# ram.net
KiCad netlist of a schematic drawn in EAGLE
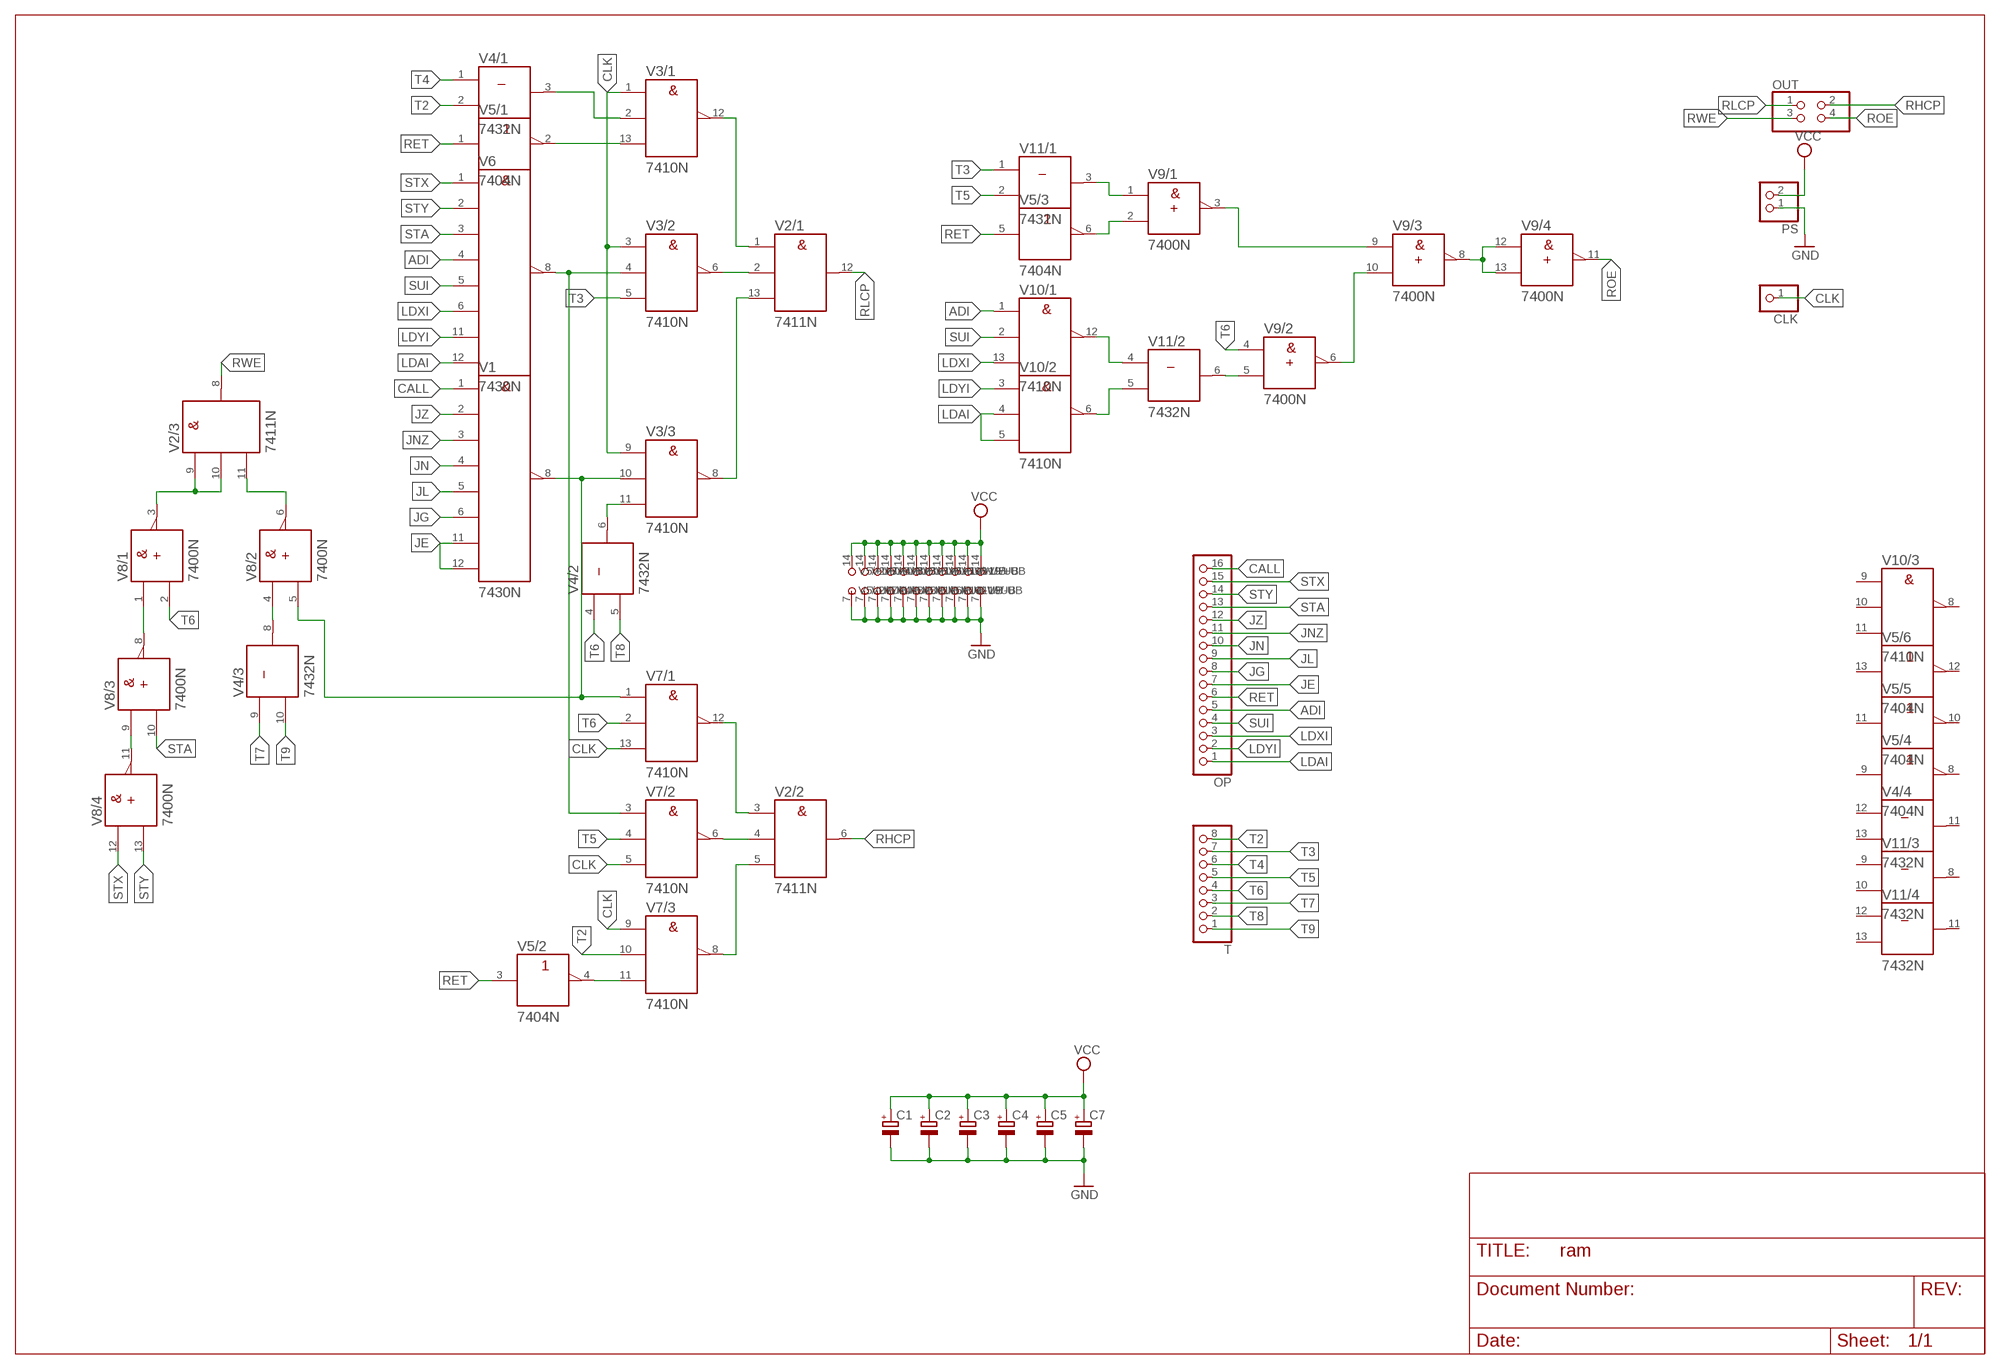
[diagram p0: schematic, sheet 1]

(export (version "E")
  (design (tool "Eeschema 10.0.6"))
  (components
    (comp (ref "C1")
      (value "CPOL-EUE2.5-6")
      (footprint "eagle-import:E2,5-6")
      (libsource (lib "eagle-import") (part "CPOL-EUE2.5-6"))
    )
    (comp (ref "C2")
      (value "CPOL-EUE2.5-6")
      (footprint "eagle-import:E2,5-6")
      (libsource (lib "eagle-import") (part "CPOL-EUE2.5-6"))
    )
    (comp (ref "C3")
      (value "CPOL-EUE2.5-6")
      (footprint "eagle-import:E2,5-6")
      (libsource (lib "eagle-import") (part "CPOL-EUE2.5-6"))
    )
    (comp (ref "C4")
      (value "CPOL-EUE2.5-6")
      (footprint "eagle-import:E2,5-6")
      (libsource (lib "eagle-import") (part "CPOL-EUE2.5-6"))
    )
    (comp (ref "C5")
      (value "CPOL-EUE2.5-6")
      (footprint "eagle-import:E2,5-6")
      (libsource (lib "eagle-import") (part "CPOL-EUE2.5-6"))
    )
    (comp (ref "C7")
      (value "CPOL-EUE2.5-6")
      (footprint "eagle-import:E2,5-6")
      (libsource (lib "eagle-import") (part "CPOL-EUE2.5-6"))
    )
    (comp (ref "CLK")
      (value "PINHD-1X1")
      (footprint "eagle-import:1X01")
      (libsource (lib "eagle-import") (part "PINHD-1X1"))
    )
    (comp (ref "OP")
      (value "PINHD-1X16")
      (footprint "eagle-import:1X16")
      (libsource (lib "eagle-import") (part "PINHD-1X16"))
    )
    (comp (ref "OUT")
      (value "PINHD-2X2")
      (footprint "eagle-import:2X02")
      (libsource (lib "eagle-import") (part "PINHD-2X2"))
    )
    (comp (ref "PS")
      (value "PINHD-1X2")
      (footprint "eagle-import:1X02")
      (libsource (lib "eagle-import") (part "PINHD-1X2"))
    )
    (comp (ref "T")
      (value "PINHD-1X8")
      (footprint "eagle-import:1X08")
      (libsource (lib "eagle-import") (part "PINHD-1X8"))
    )
    (comp (ref "V1")
      (value "7430N")
      (footprint "eagle-import:DIL14")
      (libsource (lib "eagle-import") (part "7430N"))
    )
    (comp (ref "V2")
      (value "7411N")
      (footprint "eagle-import:DIL14")
      (libsource (lib "eagle-import") (part "7411N"))
    )
    (comp (ref "V3")
      (value "7410N")
      (footprint "eagle-import:DIL14")
      (libsource (lib "eagle-import") (part "7410N"))
    )
    (comp (ref "V4")
      (value "7432N")
      (footprint "eagle-import:DIL14")
      (libsource (lib "eagle-import") (part "7432N"))
    )
    (comp (ref "V5")
      (value "7404N")
      (footprint "eagle-import:DIL14")
      (libsource (lib "eagle-import") (part "7404N"))
    )
    (comp (ref "V6")
      (value "7430N")
      (footprint "eagle-import:DIL14")
      (libsource (lib "eagle-import") (part "7430N"))
    )
    (comp (ref "V7")
      (value "7410N")
      (footprint "eagle-import:DIL14")
      (libsource (lib "eagle-import") (part "7410N"))
    )
    (comp (ref "V8")
      (value "7400N")
      (footprint "eagle-import:DIL14")
      (libsource (lib "eagle-import") (part "7400N"))
    )
    (comp (ref "V9")
      (value "7400N")
      (footprint "eagle-import:DIL14")
      (libsource (lib "eagle-import") (part "7400N"))
    )
    (comp (ref "V10")
      (value "7410N")
      (footprint "eagle-import:DIL14")
      (libsource (lib "eagle-import") (part "7410N"))
    )
    (comp (ref "V11")
      (value "7432N")
      (footprint "eagle-import:DIL14")
      (libsource (lib "eagle-import") (part "7432N"))
    )
  )
  (nets
    (net (code "1") (name "ADI") (class "Default")
      (node (ref "OP") (pin "5") (pinfunction "5_5") (pintype "passive"))
      (node (ref "V10") (pin "1") (pinfunction "A_1") (pintype "input"))
      (node (ref "V6") (pin "4") (pinfunction "D_4") (pintype "input"))
    )
    (net (code "2") (name "CALL") (class "Default")
      (node (ref "OP") (pin "16") (pinfunction "16_16") (pintype "passive"))
      (node (ref "V1") (pin "1") (pinfunction "A_1") (pintype "input"))
    )
    (net (code "3") (name "CLK") (class "Default")
      (node (ref "CLK") (pin "1") (pinfunction "1_1") (pintype "passive"))
      (node (ref "V3") (pin "1") (pinfunction "A_1") (pintype "input"))
      (node (ref "V3") (pin "3") (pinfunction "A_3") (pintype "input"))
      (node (ref "V3") (pin "9") (pinfunction "A_9") (pintype "input"))
      (node (ref "V7") (pin "13") (pinfunction "C_13") (pintype "input"))
      (node (ref "V7") (pin "5") (pinfunction "C_5") (pintype "input"))
      (node (ref "V7") (pin "9") (pinfunction "A_9") (pintype "input"))
    )
    (net (code "4") (name "GND") (class "Default")
      (node (ref "C1") (pin "-") (pinfunction "-_-") (pintype "passive"))
      (node (ref "C2") (pin "-") (pinfunction "-_-") (pintype "passive"))
      (node (ref "C3") (pin "-") (pinfunction "-_-") (pintype "passive"))
      (node (ref "C4") (pin "-") (pinfunction "-_-") (pintype "passive"))
      (node (ref "C5") (pin "-") (pinfunction "-_-") (pintype "passive"))
      (node (ref "C7") (pin "-") (pinfunction "-_-") (pintype "passive"))
      (node (ref "PS") (pin "1") (pinfunction "1_1") (pintype "passive"))
      (node (ref "V1") (pin "7") (pinfunction "-UB_7") (pintype "power_in"))
      (node (ref "V10") (pin "7") (pinfunction "-UB_7") (pintype "power_in"))
      (node (ref "V11") (pin "7") (pinfunction "-UB_7") (pintype "power_in"))
      (node (ref "V2") (pin "7") (pinfunction "-UB_7") (pintype "power_in"))
      (node (ref "V3") (pin "7") (pinfunction "-UB_7") (pintype "power_in"))
      (node (ref "V4") (pin "7") (pinfunction "-UB_7") (pintype "power_in"))
      (node (ref "V5") (pin "7") (pinfunction "-UB_7") (pintype "power_in"))
      (node (ref "V6") (pin "7") (pinfunction "-UB_7") (pintype "power_in"))
      (node (ref "V7") (pin "7") (pinfunction "-UB_7") (pintype "power_in"))
      (node (ref "V8") (pin "7") (pinfunction "-UB_7") (pintype "power_in"))
      (node (ref "V9") (pin "7") (pinfunction "-UB_7") (pintype "power_in"))
    )
    (net (code "5") (name "JE") (class "Default")
      (node (ref "OP") (pin "7") (pinfunction "7_7") (pintype "passive"))
      (node (ref "V1") (pin "11") (pinfunction "G_11") (pintype "input"))
      (node (ref "V1") (pin "12") (pinfunction "H_12") (pintype "input"))
    )
    (net (code "6") (name "JG") (class "Default")
      (node (ref "OP") (pin "8") (pinfunction "8_8") (pintype "passive"))
      (node (ref "V1") (pin "6") (pinfunction "F_6") (pintype "input"))
    )
    (net (code "7") (name "JL") (class "Default")
      (node (ref "OP") (pin "9") (pinfunction "9_9") (pintype "passive"))
      (node (ref "V1") (pin "5") (pinfunction "E_5") (pintype "input"))
    )
    (net (code "8") (name "JN") (class "Default")
      (node (ref "OP") (pin "10") (pinfunction "10_10") (pintype "passive"))
      (node (ref "V1") (pin "4") (pinfunction "D_4") (pintype "input"))
    )
    (net (code "9") (name "JNZ") (class "Default")
      (node (ref "OP") (pin "11") (pinfunction "11_11") (pintype "passive"))
      (node (ref "V1") (pin "3") (pinfunction "C_3") (pintype "input"))
    )
    (net (code "10") (name "JZ") (class "Default")
      (node (ref "OP") (pin "12") (pinfunction "12_12") (pintype "passive"))
      (node (ref "V1") (pin "2") (pinfunction "B_2") (pintype "input"))
    )
    (net (code "11") (name "LDAI") (class "Default")
      (node (ref "OP") (pin "1") (pinfunction "1_1") (pintype "passive"))
      (node (ref "V10") (pin "4") (pinfunction "B_4") (pintype "input"))
      (node (ref "V10") (pin "5") (pinfunction "C_5") (pintype "input"))
      (node (ref "V6") (pin "12") (pinfunction "H_12") (pintype "input"))
    )
    (net (code "12") (name "LDXI") (class "Default")
      (node (ref "OP") (pin "3") (pinfunction "3_3") (pintype "passive"))
      (node (ref "V10") (pin "13") (pinfunction "C_13") (pintype "input"))
      (node (ref "V6") (pin "6") (pinfunction "F_6") (pintype "input"))
    )
    (net (code "13") (name "LDYI") (class "Default")
      (node (ref "OP") (pin "2") (pinfunction "2_2") (pintype "passive"))
      (node (ref "V10") (pin "3") (pinfunction "A_3") (pintype "input"))
      (node (ref "V6") (pin "11") (pinfunction "G_11") (pintype "input"))
    )
    (net (code "14") (name "Net-(V1C-Y)") (class "Default")
      (node (ref "V1") (pin "8") (pinfunction "Y_8") (pintype "output"))
      (node (ref "V3") (pin "10") (pinfunction "B_10") (pintype "input"))
      (node (ref "V7") (pin "1") (pinfunction "A_1") (pintype "input"))
      (node (ref "V8") (pin "5") (pinfunction "B_5") (pintype "input"))
    )
    (net (code "15") (name "Net-(V2C-A)") (class "Default")
      (node (ref "V2") (pin "1") (pinfunction "A_1") (pintype "input"))
      (node (ref "V3") (pin "12") (pinfunction "Y_12") (pintype "output"))
    )
    (net (code "16") (name "Net-(V2C-B)") (class "Default")
      (node (ref "V2") (pin "2") (pinfunction "B_2") (pintype "input"))
      (node (ref "V3") (pin "6") (pinfunction "Y_6") (pintype "output"))
    )
    (net (code "17") (name "Net-(V2C-C)") (class "Default")
      (node (ref "V2") (pin "13") (pinfunction "C_13") (pintype "input"))
      (node (ref "V3") (pin "8") (pinfunction "Y_8") (pintype "output"))
    )
    (net (code "18") (name "Net-(V2D-A)") (class "Default")
      (node (ref "V2") (pin "3") (pinfunction "A_3") (pintype "input"))
      (node (ref "V7") (pin "12") (pinfunction "Y_12") (pintype "output"))
    )
    (net (code "19") (name "Net-(V2D-B)") (class "Default")
      (node (ref "V2") (pin "4") (pinfunction "B_4") (pintype "input"))
      (node (ref "V7") (pin "6") (pinfunction "Y_6") (pintype "output"))
    )
    (net (code "20") (name "Net-(V2D-C)") (class "Default")
      (node (ref "V2") (pin "5") (pinfunction "C_5") (pintype "input"))
      (node (ref "V7") (pin "8") (pinfunction "Y_8") (pintype "output"))
    )
    (net (code "21") (name "Net-(V2E-A)") (class "Default")
      (node (ref "V2") (pin "10") (pinfunction "B_10") (pintype "input"))
      (node (ref "V2") (pin "9") (pinfunction "A_9") (pintype "input"))
      (node (ref "V8") (pin "3") (pinfunction "Y_3") (pintype "output"))
    )
    (net (code "22") (name "Net-(V2E-C)") (class "Default")
      (node (ref "V2") (pin "11") (pinfunction "C_11") (pintype "input"))
      (node (ref "V8") (pin "6") (pinfunction "Y_6") (pintype "output"))
    )
    (net (code "23") (name "Net-(V3C-B)") (class "Default")
      (node (ref "V3") (pin "2") (pinfunction "B_2") (pintype "input"))
      (node (ref "V4") (pin "3") (pinfunction "Y_3") (pintype "output"))
    )
    (net (code "24") (name "Net-(V3C-C)") (class "Default")
      (node (ref "V3") (pin "13") (pinfunction "C_13") (pintype "input"))
      (node (ref "V5") (pin "2") (pinfunction "Y_2") (pintype "output"))
    )
    (net (code "25") (name "Net-(V3D-B)") (class "Default")
      (node (ref "V3") (pin "4") (pinfunction "B_4") (pintype "input"))
      (node (ref "V6") (pin "8") (pinfunction "Y_8") (pintype "output"))
      (node (ref "V7") (pin "3") (pinfunction "A_3") (pintype "input"))
    )
    (net (code "26") (name "Net-(V3E-C)") (class "Default")
      (node (ref "V3") (pin "11") (pinfunction "C_11") (pintype "input"))
      (node (ref "V4") (pin "6") (pinfunction "Y_6") (pintype "output"))
    )
    (net (code "27") (name "Net-(V4E-Y)") (class "Default")
      (node (ref "V4") (pin "8") (pinfunction "Y_8") (pintype "output"))
      (node (ref "V8") (pin "4") (pinfunction "A_4") (pintype "input"))
    )
    (net (code "28") (name "Net-(V5D-Y)") (class "Default")
      (node (ref "V5") (pin "4") (pinfunction "Y_4") (pintype "output"))
      (node (ref "V7") (pin "11") (pinfunction "C_11") (pintype "input"))
    )
    (net (code "29") (name "Net-(V5E-Y)") (class "Default")
      (node (ref "V5") (pin "6") (pinfunction "Y_6") (pintype "output"))
      (node (ref "V9") (pin "2") (pinfunction "B_2") (pintype "input"))
    )
    (net (code "30") (name "Net-(V8C-A)") (class "Default")
      (node (ref "V8") (pin "1") (pinfunction "A_1") (pintype "input"))
      (node (ref "V8") (pin "8") (pinfunction "Y_8") (pintype "output"))
    )
    (net (code "31") (name "Net-(V8E-A)") (class "Default")
      (node (ref "V8") (pin "11") (pinfunction "Y_11") (pintype "output"))
      (node (ref "V8") (pin "9") (pinfunction "A_9") (pintype "input"))
    )
    (net (code "32") (name "Net-(V9C-Y)") (class "Default")
      (node (ref "V9") (pin "3") (pinfunction "Y_3") (pintype "output"))
      (node (ref "V9") (pin "9") (pinfunction "A_9") (pintype "input"))
    )
    (net (code "33") (name "Net-(V9D-Y)") (class "Default")
      (node (ref "V9") (pin "10") (pinfunction "B_10") (pintype "input"))
      (node (ref "V9") (pin "6") (pinfunction "Y_6") (pintype "output"))
    )
    (net (code "34") (name "Net-(V9E-Y)") (class "Default")
      (node (ref "V9") (pin "12") (pinfunction "A_12") (pintype "input"))
      (node (ref "V9") (pin "13") (pinfunction "B_13") (pintype "input"))
      (node (ref "V9") (pin "8") (pinfunction "Y_8") (pintype "output"))
    )
    (net (code "35") (name "Net-(V10C-Y)") (class "Default")
      (node (ref "V10") (pin "12") (pinfunction "Y_12") (pintype "output"))
      (node (ref "V11") (pin "4") (pinfunction "A_4") (pintype "input"))
    )
    (net (code "36") (name "Net-(V10D-Y)") (class "Default")
      (node (ref "V10") (pin "6") (pinfunction "Y_6") (pintype "output"))
      (node (ref "V11") (pin "5") (pinfunction "B_5") (pintype "input"))
    )
    (net (code "37") (name "Net-(V11C-Y)") (class "Default")
      (node (ref "V11") (pin "3") (pinfunction "Y_3") (pintype "output"))
      (node (ref "V9") (pin "1") (pinfunction "A_1") (pintype "input"))
    )
    (net (code "38") (name "Net-(V11D-Y)") (class "Default")
      (node (ref "V11") (pin "6") (pinfunction "Y_6") (pintype "output"))
      (node (ref "V9") (pin "5") (pinfunction "B_5") (pintype "input"))
    )
    (net (code "39") (name "RET") (class "Default")
      (node (ref "OP") (pin "6") (pinfunction "6_6") (pintype "passive"))
      (node (ref "V5") (pin "1") (pinfunction "A_1") (pintype "input"))
      (node (ref "V5") (pin "3") (pinfunction "A_3") (pintype "input"))
      (node (ref "V5") (pin "5") (pinfunction "A_5") (pintype "input"))
    )
    (net (code "40") (name "RHCP") (class "Default")
      (node (ref "OUT") (pin "2") (pinfunction "2_2") (pintype "passive"))
      (node (ref "V2") (pin "6") (pinfunction "Y_6") (pintype "output"))
    )
    (net (code "41") (name "RLCP") (class "Default")
      (node (ref "OUT") (pin "1") (pinfunction "1_1") (pintype "passive"))
      (node (ref "V2") (pin "12") (pinfunction "Y_12") (pintype "output"))
    )
    (net (code "42") (name "ROE") (class "Default")
      (node (ref "OUT") (pin "4") (pinfunction "4_4") (pintype "passive"))
      (node (ref "V9") (pin "11") (pinfunction "Y_11") (pintype "output"))
    )
    (net (code "43") (name "RWE") (class "Default")
      (node (ref "OUT") (pin "3") (pinfunction "3_3") (pintype "passive"))
      (node (ref "V2") (pin "8") (pinfunction "Y_8") (pintype "output"))
    )
    (net (code "44") (name "STA") (class "Default")
      (node (ref "OP") (pin "13") (pinfunction "13_13") (pintype "passive"))
      (node (ref "V6") (pin "3") (pinfunction "C_3") (pintype "input"))
      (node (ref "V8") (pin "10") (pinfunction "B_10") (pintype "input"))
    )
    (net (code "45") (name "STX") (class "Default")
      (node (ref "OP") (pin "15") (pinfunction "15_15") (pintype "passive"))
      (node (ref "V6") (pin "1") (pinfunction "A_1") (pintype "input"))
      (node (ref "V8") (pin "12") (pinfunction "A_12") (pintype "input"))
    )
    (net (code "46") (name "STY") (class "Default")
      (node (ref "OP") (pin "14") (pinfunction "14_14") (pintype "passive"))
      (node (ref "V6") (pin "2") (pinfunction "B_2") (pintype "input"))
      (node (ref "V8") (pin "13") (pinfunction "B_13") (pintype "input"))
    )
    (net (code "47") (name "SUI") (class "Default")
      (node (ref "OP") (pin "4") (pinfunction "4_4") (pintype "passive"))
      (node (ref "V10") (pin "2") (pinfunction "B_2") (pintype "input"))
      (node (ref "V6") (pin "5") (pinfunction "E_5") (pintype "input"))
    )
    (net (code "48") (name "T2") (class "Default")
      (node (ref "T") (pin "8") (pinfunction "8_8") (pintype "passive"))
      (node (ref "V4") (pin "2") (pinfunction "B_2") (pintype "input"))
      (node (ref "V7") (pin "10") (pinfunction "B_10") (pintype "input"))
    )
    (net (code "49") (name "T3") (class "Default")
      (node (ref "T") (pin "7") (pinfunction "7_7") (pintype "passive"))
      (node (ref "V11") (pin "1") (pinfunction "A_1") (pintype "input"))
      (node (ref "V3") (pin "5") (pinfunction "C_5") (pintype "input"))
    )
    (net (code "50") (name "T4") (class "Default")
      (node (ref "T") (pin "6") (pinfunction "6_6") (pintype "passive"))
      (node (ref "V4") (pin "1") (pinfunction "A_1") (pintype "input"))
    )
    (net (code "51") (name "T5") (class "Default")
      (node (ref "T") (pin "5") (pinfunction "5_5") (pintype "passive"))
      (node (ref "V11") (pin "2") (pinfunction "B_2") (pintype "input"))
      (node (ref "V7") (pin "4") (pinfunction "B_4") (pintype "input"))
    )
    (net (code "52") (name "T6") (class "Default")
      (node (ref "T") (pin "4") (pinfunction "4_4") (pintype "passive"))
      (node (ref "V4") (pin "4") (pinfunction "A_4") (pintype "input"))
      (node (ref "V7") (pin "2") (pinfunction "B_2") (pintype "input"))
      (node (ref "V8") (pin "2") (pinfunction "B_2") (pintype "input"))
      (node (ref "V9") (pin "4") (pinfunction "A_4") (pintype "input"))
    )
    (net (code "53") (name "T7") (class "Default")
      (node (ref "T") (pin "3") (pinfunction "3_3") (pintype "passive"))
      (node (ref "V4") (pin "9") (pinfunction "A_9") (pintype "input"))
    )
    (net (code "54") (name "T8") (class "Default")
      (node (ref "T") (pin "2") (pinfunction "2_2") (pintype "passive"))
      (node (ref "V4") (pin "5") (pinfunction "B_5") (pintype "input"))
    )
    (net (code "55") (name "T9") (class "Default")
      (node (ref "T") (pin "1") (pinfunction "1_1") (pintype "passive"))
      (node (ref "V4") (pin "10") (pinfunction "B_10") (pintype "input"))
    )
    (net (code "56") (name "VCC") (class "Default")
      (node (ref "C1") (pin "+") (pinfunction "+_+") (pintype "passive"))
      (node (ref "C2") (pin "+") (pinfunction "+_+") (pintype "passive"))
      (node (ref "C3") (pin "+") (pinfunction "+_+") (pintype "passive"))
      (node (ref "C4") (pin "+") (pinfunction "+_+") (pintype "passive"))
      (node (ref "C5") (pin "+") (pinfunction "+_+") (pintype "passive"))
      (node (ref "C7") (pin "+") (pinfunction "+_+") (pintype "passive"))
      (node (ref "PS") (pin "2") (pinfunction "2_2") (pintype "passive"))
      (node (ref "V1") (pin "14") (pinfunction "+UB_14") (pintype "power_in"))
      (node (ref "V10") (pin "14") (pinfunction "+UB_14") (pintype "power_in"))
      (node (ref "V11") (pin "14") (pinfunction "+UB_14") (pintype "power_in"))
      (node (ref "V2") (pin "14") (pinfunction "+UB_14") (pintype "power_in"))
      (node (ref "V3") (pin "14") (pinfunction "+UB_14") (pintype "power_in"))
      (node (ref "V4") (pin "14") (pinfunction "+UB_14") (pintype "power_in"))
      (node (ref "V5") (pin "14") (pinfunction "+UB_14") (pintype "power_in"))
      (node (ref "V6") (pin "14") (pinfunction "+UB_14") (pintype "power_in"))
      (node (ref "V7") (pin "14") (pinfunction "+UB_14") (pintype "power_in"))
      (node (ref "V8") (pin "14") (pinfunction "+UB_14") (pintype "power_in"))
      (node (ref "V9") (pin "14") (pinfunction "+UB_14") (pintype "power_in"))
    )
    (net (code "57") (name "unconnected-(V4F-A-Pad12)") (class "Default")
      (node (ref "V4") (pin "12") (pinfunction "A_12") (pintype "input"))
    )
    (net (code "58") (name "unconnected-(V4F-B-Pad13)") (class "Default")
      (node (ref "V4") (pin "13") (pinfunction "B_13") (pintype "input"))
    )
    (net (code "59") (name "unconnected-(V4F-Y-Pad11)") (class "Default")
      (node (ref "V4") (pin "11") (pinfunction "Y_11") (pintype "output"))
    )
    (net (code "60") (name "unconnected-(V5F-A-Pad9)") (class "Default")
      (node (ref "V5") (pin "9") (pinfunction "A_9") (pintype "input"))
    )
    (net (code "61") (name "unconnected-(V5F-Y-Pad8)") (class "Default")
      (node (ref "V5") (pin "8") (pinfunction "Y_8") (pintype "output"))
    )
    (net (code "62") (name "unconnected-(V5G-A-Pad11)") (class "Default")
      (node (ref "V5") (pin "11") (pinfunction "A_11") (pintype "input"))
    )
    (net (code "63") (name "unconnected-(V5G-Y-Pad10)") (class "Default")
      (node (ref "V5") (pin "10") (pinfunction "Y_10") (pintype "output"))
    )
    (net (code "64") (name "unconnected-(V5H-A-Pad13)") (class "Default")
      (node (ref "V5") (pin "13") (pinfunction "A_13") (pintype "input"))
    )
    (net (code "65") (name "unconnected-(V5H-Y-Pad12)") (class "Default")
      (node (ref "V5") (pin "12") (pinfunction "Y_12") (pintype "output"))
    )
    (net (code "66") (name "unconnected-(V10E-A-Pad9)") (class "Default")
      (node (ref "V10") (pin "9") (pinfunction "A_9") (pintype "input"))
    )
    (net (code "67") (name "unconnected-(V10E-B-Pad10)") (class "Default")
      (node (ref "V10") (pin "10") (pinfunction "B_10") (pintype "input"))
    )
    (net (code "68") (name "unconnected-(V10E-C-Pad11)") (class "Default")
      (node (ref "V10") (pin "11") (pinfunction "C_11") (pintype "input"))
    )
    (net (code "69") (name "unconnected-(V10E-Y-Pad8)") (class "Default")
      (node (ref "V10") (pin "8") (pinfunction "Y_8") (pintype "output"))
    )
    (net (code "70") (name "unconnected-(V11E-A-Pad9)") (class "Default")
      (node (ref "V11") (pin "9") (pinfunction "A_9") (pintype "input"))
    )
    (net (code "71") (name "unconnected-(V11E-B-Pad10)") (class "Default")
      (node (ref "V11") (pin "10") (pinfunction "B_10") (pintype "input"))
    )
    (net (code "72") (name "unconnected-(V11E-Y-Pad8)") (class "Default")
      (node (ref "V11") (pin "8") (pinfunction "Y_8") (pintype "output"))
    )
    (net (code "73") (name "unconnected-(V11F-A-Pad12)") (class "Default")
      (node (ref "V11") (pin "12") (pinfunction "A_12") (pintype "input"))
    )
    (net (code "74") (name "unconnected-(V11F-B-Pad13)") (class "Default")
      (node (ref "V11") (pin "13") (pinfunction "B_13") (pintype "input"))
    )
    (net (code "75") (name "unconnected-(V11F-Y-Pad11)") (class "Default")
      (node (ref "V11") (pin "11") (pinfunction "Y_11") (pintype "output"))
    )
  )
)
